# driver.net
KiCad netlist of a schematic drawn in EAGLE
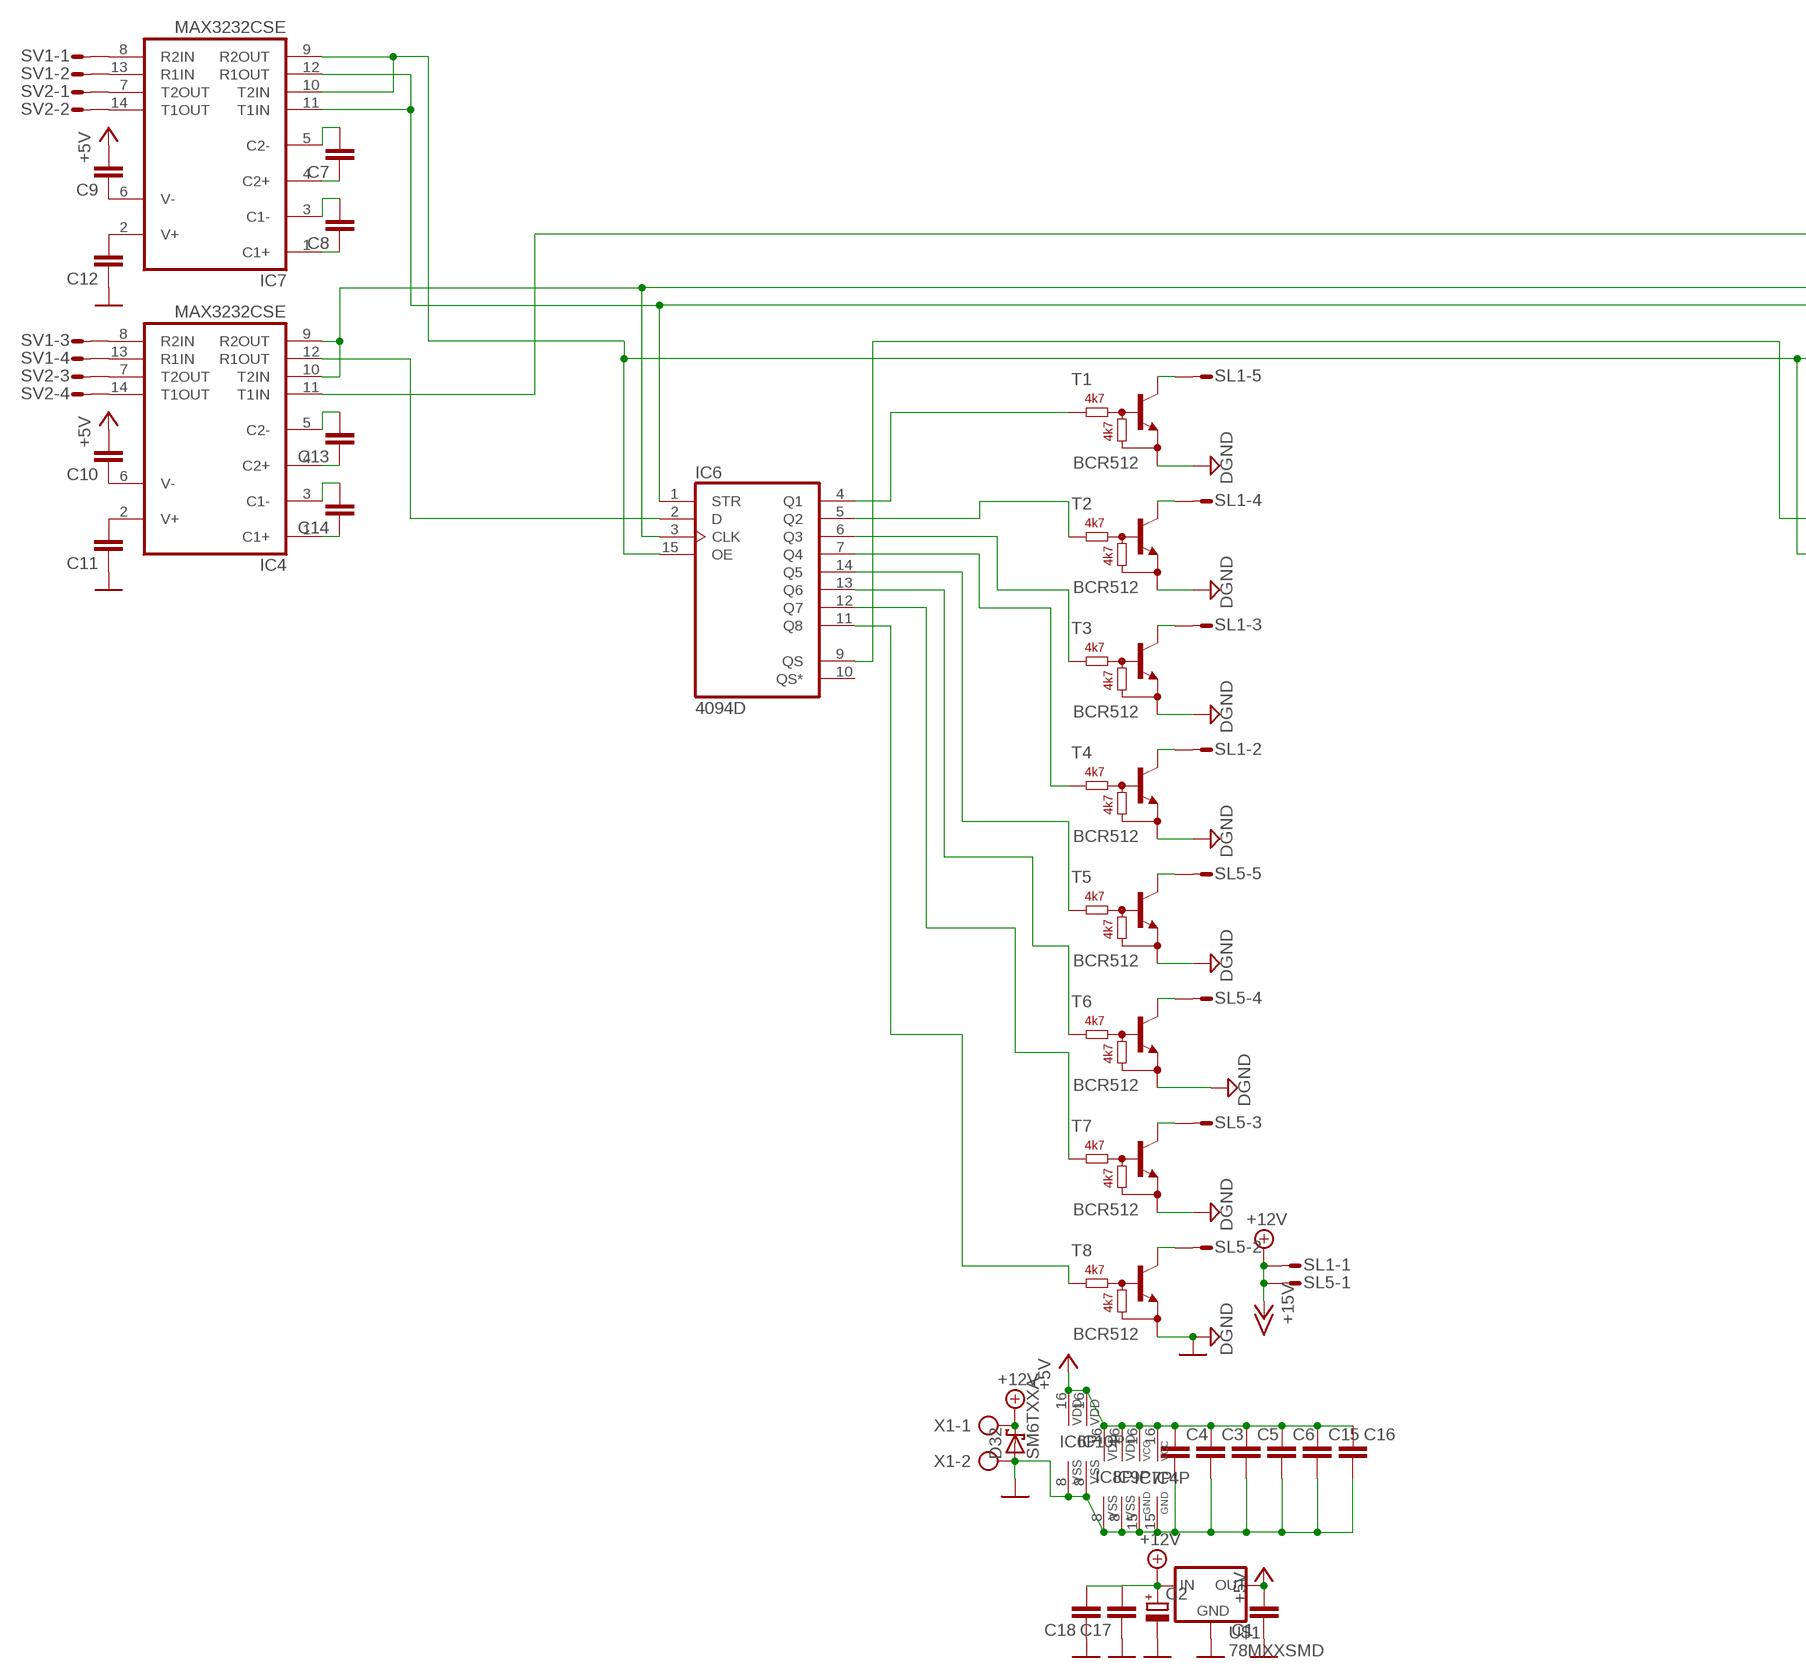
[diagram p0: schematic, sheet 1, part 1 of 2]
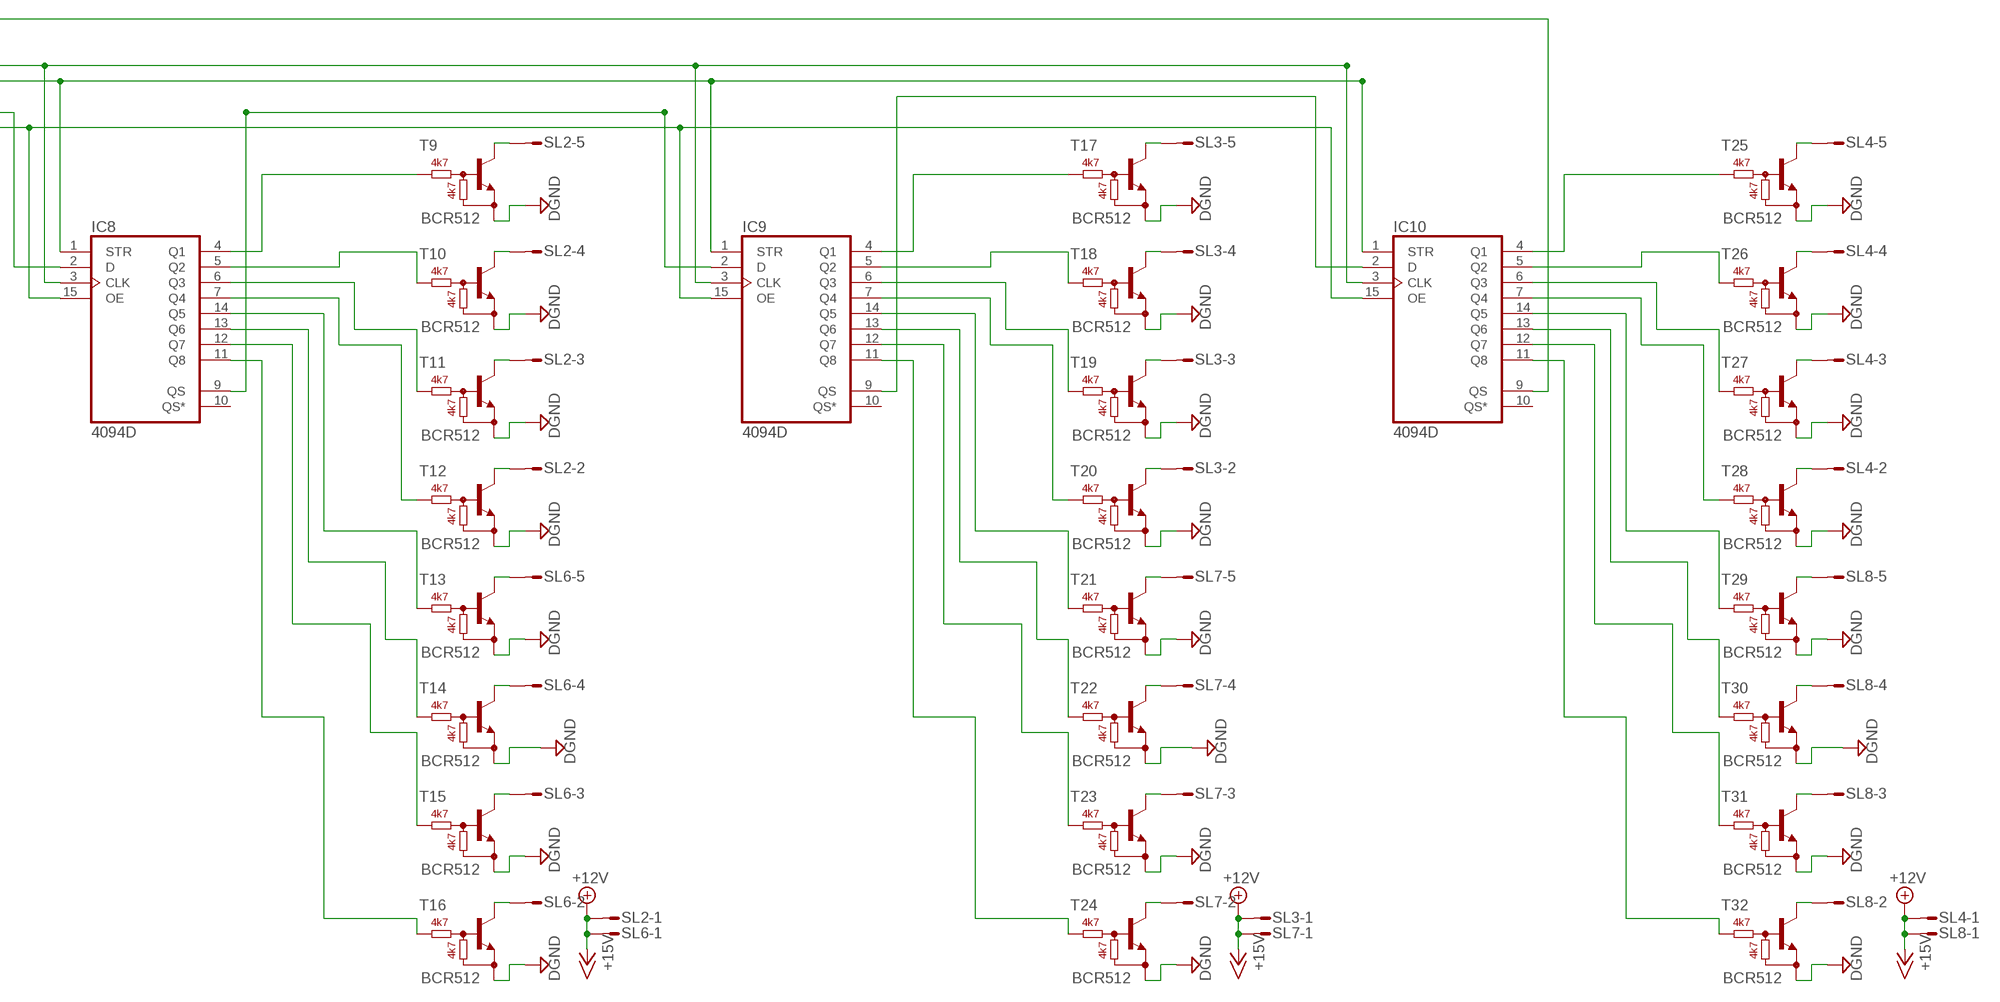
[diagram p1: schematic, sheet 1, part 2 of 2]

(export (version "E")
  (design (tool "Eeschema 10.0.6"))
  (components
    (comp (ref "C1")
      (value "C-EUC0603")
      (footprint "eagle-import:C0603")
      (libsource (lib "eagle-import") (part "C-EUC0603"))
    )
    (comp (ref "C2")
      (value "CPOL-EUSMCD")
      (footprint "eagle-import:SMC_D")
      (libsource (lib "eagle-import") (part "CPOL-EUSMCD"))
    )
    (comp (ref "C3")
      (value "C-EUC0603")
      (footprint "eagle-import:C0603")
      (libsource (lib "eagle-import") (part "C-EUC0603"))
    )
    (comp (ref "C4")
      (value "C-EUC0603")
      (footprint "eagle-import:C0603")
      (libsource (lib "eagle-import") (part "C-EUC0603"))
    )
    (comp (ref "C5")
      (value "C-EUC0603")
      (footprint "eagle-import:C0603")
      (libsource (lib "eagle-import") (part "C-EUC0603"))
    )
    (comp (ref "C6")
      (value "C-EUC0603")
      (footprint "eagle-import:C0603")
      (libsource (lib "eagle-import") (part "C-EUC0603"))
    )
    (comp (ref "C7")
      (value "C-EUC0603")
      (footprint "eagle-import:C0603")
      (libsource (lib "eagle-import") (part "C-EUC0603"))
    )
    (comp (ref "C8")
      (value "C-EUC0603")
      (footprint "eagle-import:C0603")
      (libsource (lib "eagle-import") (part "C-EUC0603"))
    )
    (comp (ref "C9")
      (value "C-EUC0603")
      (footprint "eagle-import:C0603")
      (libsource (lib "eagle-import") (part "C-EUC0603"))
    )
    (comp (ref "C10")
      (value "C-EUC0603")
      (footprint "eagle-import:C0603")
      (libsource (lib "eagle-import") (part "C-EUC0603"))
    )
    (comp (ref "C11")
      (value "C-EUC0603")
      (footprint "eagle-import:C0603")
      (libsource (lib "eagle-import") (part "C-EUC0603"))
    )
    (comp (ref "C12")
      (value "C-EUC0603")
      (footprint "eagle-import:C0603")
      (libsource (lib "eagle-import") (part "C-EUC0603"))
    )
    (comp (ref "C13")
      (value "C-EUC0603")
      (footprint "eagle-import:C0603")
      (libsource (lib "eagle-import") (part "C-EUC0603"))
    )
    (comp (ref "C14")
      (value "C-EUC0603")
      (footprint "eagle-import:C0603")
      (libsource (lib "eagle-import") (part "C-EUC0603"))
    )
    (comp (ref "C15")
      (value "C-EUC0603")
      (footprint "eagle-import:C0603")
      (libsource (lib "eagle-import") (part "C-EUC0603"))
    )
    (comp (ref "C16")
      (value "C-EUC0603")
      (footprint "eagle-import:C0603")
      (libsource (lib "eagle-import") (part "C-EUC0603"))
    )
    (comp (ref "C17")
      (value "C-EUC0603")
      (footprint "eagle-import:C0603")
      (libsource (lib "eagle-import") (part "C-EUC0603"))
    )
    (comp (ref "C18")
      (value "C-EUC0603")
      (footprint "eagle-import:C0603")
      (libsource (lib "eagle-import") (part "C-EUC0603"))
    )
    (comp (ref "D32")
      (value "SM6TXXA")
      (footprint "eagle-import:SMB")
      (libsource (lib "eagle-import") (part "SM6TXXA"))
    )
    (comp (ref "IC4")
      (value "MAX3232CSE")
      (footprint "eagle-import:SO16")
      (fields (field (name "OC_FARNELL") "1470443"))
      (libsource (lib "eagle-import") (part "MAX3232SEC"))
    )
    (comp (ref "IC6")
      (value "4094D")
      (footprint "eagle-import:SO16")
      (fields (field (name "OC_FARNELL") "1740132"))
      (libsource (lib "eagle-import") (part "4094D"))
    )
    (comp (ref "IC7")
      (value "MAX3232CSE")
      (footprint "eagle-import:SO16")
      (fields (field (name "OC_FARNELL") "1470443"))
      (libsource (lib "eagle-import") (part "MAX3232SEC"))
    )
    (comp (ref "IC8")
      (value "4094D")
      (footprint "eagle-import:SO16")
      (fields (field (name "OC_FARNELL") "1740132"))
      (libsource (lib "eagle-import") (part "4094D"))
    )
    (comp (ref "IC9")
      (value "4094D")
      (footprint "eagle-import:SO16")
      (fields (field (name "OC_FARNELL") "1740132"))
      (libsource (lib "eagle-import") (part "4094D"))
    )
    (comp (ref "IC10")
      (value "4094D")
      (footprint "eagle-import:SO16")
      (fields (field (name "OC_FARNELL") "1740132"))
      (libsource (lib "eagle-import") (part "4094D"))
    )
    (comp (ref "SL1")
      (value "M05S")
      (footprint "eagle-import:05P")
      (libsource (lib "eagle-import") (part "M05S"))
    )
    (comp (ref "SL2")
      (value "M05S")
      (footprint "eagle-import:05P")
      (libsource (lib "eagle-import") (part "M05S"))
    )
    (comp (ref "SL3")
      (value "M05S")
      (footprint "eagle-import:05P")
      (libsource (lib "eagle-import") (part "M05S"))
    )
    (comp (ref "SL4")
      (value "M05S")
      (footprint "eagle-import:05P")
      (libsource (lib "eagle-import") (part "M05S"))
    )
    (comp (ref "SL5")
      (value "M05S")
      (footprint "eagle-import:05P")
      (libsource (lib "eagle-import") (part "M05S"))
    )
    (comp (ref "SL6")
      (value "M05S")
      (footprint "eagle-import:05P")
      (libsource (lib "eagle-import") (part "M05S"))
    )
    (comp (ref "SL7")
      (value "M05S")
      (footprint "eagle-import:05P")
      (libsource (lib "eagle-import") (part "M05S"))
    )
    (comp (ref "SL8")
      (value "M05S")
      (footprint "eagle-import:05P")
      (libsource (lib "eagle-import") (part "M05S"))
    )
    (comp (ref "SV1")
      (value "S04P")
      (footprint "eagle-import:S04P")
      (libsource (lib "eagle-import") (part "S04P"))
    )
    (comp (ref "SV2")
      (value "S04P")
      (footprint "eagle-import:S04P")
      (libsource (lib "eagle-import") (part "S04P"))
    )
    (comp (ref "T1")
      (value "BCR512")
      (footprint "eagle-import:SOT23-R_INFINEON")
      (libsource (lib "eagle-import") (part "BCR512"))
    )
    (comp (ref "T2")
      (value "BCR512")
      (footprint "eagle-import:SOT23-R_INFINEON")
      (libsource (lib "eagle-import") (part "BCR512"))
    )
    (comp (ref "T3")
      (value "BCR512")
      (footprint "eagle-import:SOT23-R_INFINEON")
      (libsource (lib "eagle-import") (part "BCR512"))
    )
    (comp (ref "T4")
      (value "BCR512")
      (footprint "eagle-import:SOT23-R_INFINEON")
      (libsource (lib "eagle-import") (part "BCR512"))
    )
    (comp (ref "T5")
      (value "BCR512")
      (footprint "eagle-import:SOT23-R_INFINEON")
      (libsource (lib "eagle-import") (part "BCR512"))
    )
    (comp (ref "T6")
      (value "BCR512")
      (footprint "eagle-import:SOT23-R_INFINEON")
      (libsource (lib "eagle-import") (part "BCR512"))
    )
    (comp (ref "T7")
      (value "BCR512")
      (footprint "eagle-import:SOT23-R_INFINEON")
      (libsource (lib "eagle-import") (part "BCR512"))
    )
    (comp (ref "T8")
      (value "BCR512")
      (footprint "eagle-import:SOT23-R_INFINEON")
      (libsource (lib "eagle-import") (part "BCR512"))
    )
    (comp (ref "T9")
      (value "BCR512")
      (footprint "eagle-import:SOT23-R_INFINEON")
      (libsource (lib "eagle-import") (part "BCR512"))
    )
    (comp (ref "T10")
      (value "BCR512")
      (footprint "eagle-import:SOT23-R_INFINEON")
      (libsource (lib "eagle-import") (part "BCR512"))
    )
    (comp (ref "T11")
      (value "BCR512")
      (footprint "eagle-import:SOT23-R_INFINEON")
      (libsource (lib "eagle-import") (part "BCR512"))
    )
    (comp (ref "T12")
      (value "BCR512")
      (footprint "eagle-import:SOT23-R_INFINEON")
      (libsource (lib "eagle-import") (part "BCR512"))
    )
    (comp (ref "T13")
      (value "BCR512")
      (footprint "eagle-import:SOT23-R_INFINEON")
      (libsource (lib "eagle-import") (part "BCR512"))
    )
    (comp (ref "T14")
      (value "BCR512")
      (footprint "eagle-import:SOT23-R_INFINEON")
      (libsource (lib "eagle-import") (part "BCR512"))
    )
    (comp (ref "T15")
      (value "BCR512")
      (footprint "eagle-import:SOT23-R_INFINEON")
      (libsource (lib "eagle-import") (part "BCR512"))
    )
    (comp (ref "T16")
      (value "BCR512")
      (footprint "eagle-import:SOT23-R_INFINEON")
      (libsource (lib "eagle-import") (part "BCR512"))
    )
    (comp (ref "T17")
      (value "BCR512")
      (footprint "eagle-import:SOT23-R_INFINEON")
      (libsource (lib "eagle-import") (part "BCR512"))
    )
    (comp (ref "T18")
      (value "BCR512")
      (footprint "eagle-import:SOT23-R_INFINEON")
      (libsource (lib "eagle-import") (part "BCR512"))
    )
    (comp (ref "T19")
      (value "BCR512")
      (footprint "eagle-import:SOT23-R_INFINEON")
      (libsource (lib "eagle-import") (part "BCR512"))
    )
    (comp (ref "T20")
      (value "BCR512")
      (footprint "eagle-import:SOT23-R_INFINEON")
      (libsource (lib "eagle-import") (part "BCR512"))
    )
    (comp (ref "T21")
      (value "BCR512")
      (footprint "eagle-import:SOT23-R_INFINEON")
      (libsource (lib "eagle-import") (part "BCR512"))
    )
    (comp (ref "T22")
      (value "BCR512")
      (footprint "eagle-import:SOT23-R_INFINEON")
      (libsource (lib "eagle-import") (part "BCR512"))
    )
    (comp (ref "T23")
      (value "BCR512")
      (footprint "eagle-import:SOT23-R_INFINEON")
      (libsource (lib "eagle-import") (part "BCR512"))
    )
    (comp (ref "T24")
      (value "BCR512")
      (footprint "eagle-import:SOT23-R_INFINEON")
      (libsource (lib "eagle-import") (part "BCR512"))
    )
    (comp (ref "T25")
      (value "BCR512")
      (footprint "eagle-import:SOT23-R_INFINEON")
      (libsource (lib "eagle-import") (part "BCR512"))
    )
    (comp (ref "T26")
      (value "BCR512")
      (footprint "eagle-import:SOT23-R_INFINEON")
      (libsource (lib "eagle-import") (part "BCR512"))
    )
    (comp (ref "T27")
      (value "BCR512")
      (footprint "eagle-import:SOT23-R_INFINEON")
      (libsource (lib "eagle-import") (part "BCR512"))
    )
    (comp (ref "T28")
      (value "BCR512")
      (footprint "eagle-import:SOT23-R_INFINEON")
      (libsource (lib "eagle-import") (part "BCR512"))
    )
    (comp (ref "T29")
      (value "BCR512")
      (footprint "eagle-import:SOT23-R_INFINEON")
      (libsource (lib "eagle-import") (part "BCR512"))
    )
    (comp (ref "T30")
      (value "BCR512")
      (footprint "eagle-import:SOT23-R_INFINEON")
      (libsource (lib "eagle-import") (part "BCR512"))
    )
    (comp (ref "T31")
      (value "BCR512")
      (footprint "eagle-import:SOT23-R_INFINEON")
      (libsource (lib "eagle-import") (part "BCR512"))
    )
    (comp (ref "T32")
      (value "BCR512")
      (footprint "eagle-import:SOT23-R_INFINEON")
      (libsource (lib "eagle-import") (part "BCR512"))
    )
    (comp (ref "U$1")
      (value "78MXXSMD")
      (footprint "eagle-import:DPACK")
      (libsource (lib "eagle-import") (part "78MXXSMD"))
    )
    (comp (ref "X1")
      (value "AK500/2")
      (footprint "eagle-import:AK500_2")
      (libsource (lib "eagle-import") (part "AK500/2"))
    )
  )
  (nets
    (net (code "1") (name "+5V") (class "Default")
      (node (ref "C1") (pin "2") (pinfunction "2_2") (pintype "passive"))
      (node (ref "C10") (pin "2") (pinfunction "2_2") (pintype "passive"))
      (node (ref "C15") (pin "1") (pinfunction "1_1") (pintype "passive"))
      (node (ref "C16") (pin "1") (pinfunction "1_1") (pintype "passive"))
      (node (ref "C3") (pin "1") (pinfunction "1_1") (pintype "passive"))
      (node (ref "C4") (pin "1") (pinfunction "1_1") (pintype "passive"))
      (node (ref "C5") (pin "1") (pinfunction "1_1") (pintype "passive"))
      (node (ref "C6") (pin "1") (pinfunction "1_1") (pintype "passive"))
      (node (ref "C9") (pin "2") (pinfunction "2_2") (pintype "passive"))
      (node (ref "IC10") (pin "16") (pinfunction "VDD_16") (pintype "power_in"))
      (node (ref "IC4") (pin "16") (pinfunction "VCC_16") (pintype "power_in"))
      (node (ref "IC6") (pin "16") (pinfunction "VDD_16") (pintype "power_in"))
      (node (ref "IC7") (pin "16") (pinfunction "VCC_16") (pintype "power_in"))
      (node (ref "IC8") (pin "16") (pinfunction "VDD_16") (pintype "power_in"))
      (node (ref "IC9") (pin "16") (pinfunction "VDD_16") (pintype "power_in"))
      (node (ref "U$1") (pin "3") (pinfunction "OUT_3") (pintype "passive"))
    )
    (net (code "2") (name "+12V") (class "Default")
      (node (ref "C17") (pin "2") (pinfunction "2_2") (pintype "passive"))
      (node (ref "C18") (pin "2") (pinfunction "2_2") (pintype "passive"))
      (node (ref "C2") (pin "+") (pinfunction "+_+") (pintype "passive"))
      (node (ref "D32") (pin "C") (pinfunction "C_C") (pintype "passive"))
      (node (ref "SL1") (pin "1") (pinfunction "S_1") (pintype "passive"))
      (node (ref "SL2") (pin "1") (pinfunction "S_1") (pintype "passive"))
      (node (ref "SL3") (pin "1") (pinfunction "S_1") (pintype "passive"))
      (node (ref "SL4") (pin "1") (pinfunction "S_1") (pintype "passive"))
      (node (ref "SL5") (pin "1") (pinfunction "S_1") (pintype "passive"))
      (node (ref "SL6") (pin "1") (pinfunction "S_1") (pintype "passive"))
      (node (ref "SL7") (pin "1") (pinfunction "S_1") (pintype "passive"))
      (node (ref "SL8") (pin "1") (pinfunction "S_1") (pintype "passive"))
      (node (ref "U$1") (pin "1") (pinfunction "IN_1") (pintype "input"))
      (node (ref "X1") (pin "1") (pinfunction "KL_1") (pintype "passive"))
    )
    (net (code "3") (name "DGND") (class "Default")
      (node (ref "C1") (pin "1") (pinfunction "1_1") (pintype "passive"))
      (node (ref "C11") (pin "1") (pinfunction "1_1") (pintype "passive"))
      (node (ref "C12") (pin "1") (pinfunction "1_1") (pintype "passive"))
      (node (ref "C15") (pin "2") (pinfunction "2_2") (pintype "passive"))
      (node (ref "C16") (pin "2") (pinfunction "2_2") (pintype "passive"))
      (node (ref "C17") (pin "1") (pinfunction "1_1") (pintype "passive"))
      (node (ref "C18") (pin "1") (pinfunction "1_1") (pintype "passive"))
      (node (ref "C2") (pin "-") (pinfunction "-_-") (pintype "passive"))
      (node (ref "C3") (pin "2") (pinfunction "2_2") (pintype "passive"))
      (node (ref "C4") (pin "2") (pinfunction "2_2") (pintype "passive"))
      (node (ref "C5") (pin "2") (pinfunction "2_2") (pintype "passive"))
      (node (ref "C6") (pin "2") (pinfunction "2_2") (pintype "passive"))
      (node (ref "D32") (pin "A") (pinfunction "A_A") (pintype "passive"))
      (node (ref "IC10") (pin "8") (pinfunction "VSS_8") (pintype "power_in"))
      (node (ref "IC4") (pin "15") (pinfunction "GND_15") (pintype "power_in"))
      (node (ref "IC6") (pin "8") (pinfunction "VSS_8") (pintype "power_in"))
      (node (ref "IC7") (pin "15") (pinfunction "GND_15") (pintype "power_in"))
      (node (ref "IC8") (pin "8") (pinfunction "VSS_8") (pintype "power_in"))
      (node (ref "IC9") (pin "8") (pinfunction "VSS_8") (pintype "power_in"))
      (node (ref "T1") (pin "2") (pinfunction "E_2") (pintype "passive"))
      (node (ref "T10") (pin "2") (pinfunction "E_2") (pintype "passive"))
      (node (ref "T11") (pin "2") (pinfunction "E_2") (pintype "passive"))
      (node (ref "T12") (pin "2") (pinfunction "E_2") (pintype "passive"))
      (node (ref "T13") (pin "2") (pinfunction "E_2") (pintype "passive"))
      (node (ref "T14") (pin "2") (pinfunction "E_2") (pintype "passive"))
      (node (ref "T15") (pin "2") (pinfunction "E_2") (pintype "passive"))
      (node (ref "T16") (pin "2") (pinfunction "E_2") (pintype "passive"))
      (node (ref "T17") (pin "2") (pinfunction "E_2") (pintype "passive"))
      (node (ref "T18") (pin "2") (pinfunction "E_2") (pintype "passive"))
      (node (ref "T19") (pin "2") (pinfunction "E_2") (pintype "passive"))
      (node (ref "T2") (pin "2") (pinfunction "E_2") (pintype "passive"))
      (node (ref "T20") (pin "2") (pinfunction "E_2") (pintype "passive"))
      (node (ref "T21") (pin "2") (pinfunction "E_2") (pintype "passive"))
      (node (ref "T22") (pin "2") (pinfunction "E_2") (pintype "passive"))
      (node (ref "T23") (pin "2") (pinfunction "E_2") (pintype "passive"))
      (node (ref "T24") (pin "2") (pinfunction "E_2") (pintype "passive"))
      (node (ref "T25") (pin "2") (pinfunction "E_2") (pintype "passive"))
      (node (ref "T26") (pin "2") (pinfunction "E_2") (pintype "passive"))
      (node (ref "T27") (pin "2") (pinfunction "E_2") (pintype "passive"))
      (node (ref "T28") (pin "2") (pinfunction "E_2") (pintype "passive"))
      (node (ref "T29") (pin "2") (pinfunction "E_2") (pintype "passive"))
      (node (ref "T3") (pin "2") (pinfunction "E_2") (pintype "passive"))
      (node (ref "T30") (pin "2") (pinfunction "E_2") (pintype "passive"))
      (node (ref "T31") (pin "2") (pinfunction "E_2") (pintype "passive"))
      (node (ref "T32") (pin "2") (pinfunction "E_2") (pintype "passive"))
      (node (ref "T4") (pin "2") (pinfunction "E_2") (pintype "passive"))
      (node (ref "T5") (pin "2") (pinfunction "E_2") (pintype "passive"))
      (node (ref "T6") (pin "2") (pinfunction "E_2") (pintype "passive"))
      (node (ref "T7") (pin "2") (pinfunction "E_2") (pintype "passive"))
      (node (ref "T8") (pin "2") (pinfunction "E_2") (pintype "passive"))
      (node (ref "T9") (pin "2") (pinfunction "E_2") (pintype "passive"))
      (node (ref "U$1") (pin "4") (pinfunction "GND_4") (pintype "input"))
      (node (ref "X1") (pin "2") (pinfunction "KL_2") (pintype "passive"))
    )
    (net (code "4") (name "Net-(IC4A-C1+)") (class "Default")
      (node (ref "C14") (pin "1") (pinfunction "1_1") (pintype "passive"))
      (node (ref "IC4") (pin "1") (pinfunction "C1+_1") (pintype "bidirectional"))
    )
    (net (code "5") (name "Net-(IC4A-C1-)") (class "Default")
      (node (ref "C14") (pin "2") (pinfunction "2_2") (pintype "passive"))
      (node (ref "IC4") (pin "3") (pinfunction "C1-_3") (pintype "bidirectional"))
    )
    (net (code "6") (name "Net-(IC4A-C2+)") (class "Default")
      (node (ref "C13") (pin "1") (pinfunction "1_1") (pintype "passive"))
      (node (ref "IC4") (pin "4") (pinfunction "C2+_4") (pintype "bidirectional"))
    )
    (net (code "7") (name "Net-(IC4A-C2-)") (class "Default")
      (node (ref "C13") (pin "2") (pinfunction "2_2") (pintype "passive"))
      (node (ref "IC4") (pin "5") (pinfunction "C2-_5") (pintype "bidirectional"))
    )
    (net (code "8") (name "Net-(IC4A-R1IN)") (class "Default")
      (node (ref "IC4") (pin "13") (pinfunction "R1IN_13") (pintype "input"))
      (node (ref "SV1") (pin "4") (pinfunction "S_4") (pintype "passive"))
    )
    (net (code "9") (name "Net-(IC4A-R1OUT)") (class "Default")
      (node (ref "IC4") (pin "12") (pinfunction "R1OUT_12") (pintype "output"))
      (node (ref "IC6") (pin "2") (pinfunction "D_2") (pintype "input"))
    )
    (net (code "10") (name "Net-(IC4A-R2IN)") (class "Default")
      (node (ref "IC4") (pin "8") (pinfunction "R2IN_8") (pintype "input"))
      (node (ref "SV1") (pin "3") (pinfunction "S_3") (pintype "passive"))
    )
    (net (code "11") (name "Net-(IC4A-T1OUT)") (class "Default")
      (node (ref "IC4") (pin "14") (pinfunction "T1OUT_14") (pintype "output"))
      (node (ref "SV2") (pin "4") (pinfunction "S_4") (pintype "passive"))
    )
    (net (code "12") (name "Net-(IC4A-T2OUT)") (class "Default")
      (node (ref "IC4") (pin "7") (pinfunction "T2OUT_7") (pintype "output"))
      (node (ref "SV2") (pin "3") (pinfunction "S_3") (pintype "passive"))
    )
    (net (code "13") (name "Net-(IC4A-V+)") (class "Default")
      (node (ref "C11") (pin "2") (pinfunction "2_2") (pintype "passive"))
      (node (ref "IC4") (pin "2") (pinfunction "V+_2") (pintype "bidirectional"))
    )
    (net (code "14") (name "Net-(IC4A-V-)") (class "Default")
      (node (ref "C10") (pin "1") (pinfunction "1_1") (pintype "passive"))
      (node (ref "IC4") (pin "6") (pinfunction "V-_6") (pintype "bidirectional"))
    )
    (net (code "15") (name "Net-(IC6A-Q1)") (class "Default")
      (node (ref "IC6") (pin "4") (pinfunction "Q1_4") (pintype "output"))
      (node (ref "T1") (pin "1") (pinfunction "B_1") (pintype "passive"))
    )
    (net (code "16") (name "Net-(IC6A-Q2)") (class "Default")
      (node (ref "IC6") (pin "5") (pinfunction "Q2_5") (pintype "output"))
      (node (ref "T2") (pin "1") (pinfunction "B_1") (pintype "passive"))
    )
    (net (code "17") (name "Net-(IC6A-Q3)") (class "Default")
      (node (ref "IC6") (pin "6") (pinfunction "Q3_6") (pintype "output"))
      (node (ref "T3") (pin "1") (pinfunction "B_1") (pintype "passive"))
    )
    (net (code "18") (name "Net-(IC6A-Q4)") (class "Default")
      (node (ref "IC6") (pin "7") (pinfunction "Q4_7") (pintype "output"))
      (node (ref "T4") (pin "1") (pinfunction "B_1") (pintype "passive"))
    )
    (net (code "19") (name "Net-(IC6A-Q5)") (class "Default")
      (node (ref "IC6") (pin "14") (pinfunction "Q5_14") (pintype "output"))
      (node (ref "T5") (pin "1") (pinfunction "B_1") (pintype "passive"))
    )
    (net (code "20") (name "Net-(IC6A-Q6)") (class "Default")
      (node (ref "IC6") (pin "13") (pinfunction "Q6_13") (pintype "output"))
      (node (ref "T6") (pin "1") (pinfunction "B_1") (pintype "passive"))
    )
    (net (code "21") (name "Net-(IC6A-Q7)") (class "Default")
      (node (ref "IC6") (pin "12") (pinfunction "Q7_12") (pintype "output"))
      (node (ref "T7") (pin "1") (pinfunction "B_1") (pintype "passive"))
    )
    (net (code "22") (name "Net-(IC6A-Q8)") (class "Default")
      (node (ref "IC6") (pin "11") (pinfunction "Q8_11") (pintype "output"))
      (node (ref "T8") (pin "1") (pinfunction "B_1") (pintype "passive"))
    )
    (net (code "23") (name "Net-(IC6A-QS)") (class "Default")
      (node (ref "IC6") (pin "9") (pinfunction "QS_9") (pintype "output"))
      (node (ref "IC8") (pin "2") (pinfunction "D_2") (pintype "input"))
    )
    (net (code "24") (name "Net-(IC7A-C1+)") (class "Default")
      (node (ref "C8") (pin "1") (pinfunction "1_1") (pintype "passive"))
      (node (ref "IC7") (pin "1") (pinfunction "C1+_1") (pintype "bidirectional"))
    )
    (net (code "25") (name "Net-(IC7A-C1-)") (class "Default")
      (node (ref "C8") (pin "2") (pinfunction "2_2") (pintype "passive"))
      (node (ref "IC7") (pin "3") (pinfunction "C1-_3") (pintype "bidirectional"))
    )
    (net (code "26") (name "Net-(IC7A-C2+)") (class "Default")
      (node (ref "C7") (pin "1") (pinfunction "1_1") (pintype "passive"))
      (node (ref "IC7") (pin "4") (pinfunction "C2+_4") (pintype "bidirectional"))
    )
    (net (code "27") (name "Net-(IC7A-C2-)") (class "Default")
      (node (ref "C7") (pin "2") (pinfunction "2_2") (pintype "passive"))
      (node (ref "IC7") (pin "5") (pinfunction "C2-_5") (pintype "bidirectional"))
    )
    (net (code "28") (name "Net-(IC7A-R1IN)") (class "Default")
      (node (ref "IC7") (pin "13") (pinfunction "R1IN_13") (pintype "input"))
      (node (ref "SV1") (pin "2") (pinfunction "S_2") (pintype "passive"))
    )
    (net (code "29") (name "Net-(IC7A-R2IN)") (class "Default")
      (node (ref "IC7") (pin "8") (pinfunction "R2IN_8") (pintype "input"))
      (node (ref "SV1") (pin "1") (pinfunction "S_1") (pintype "passive"))
    )
    (net (code "30") (name "Net-(IC7A-T1OUT)") (class "Default")
      (node (ref "IC7") (pin "14") (pinfunction "T1OUT_14") (pintype "output"))
      (node (ref "SV2") (pin "2") (pinfunction "S_2") (pintype "passive"))
    )
    (net (code "31") (name "Net-(IC7A-T2OUT)") (class "Default")
      (node (ref "IC7") (pin "7") (pinfunction "T2OUT_7") (pintype "output"))
      (node (ref "SV2") (pin "1") (pinfunction "S_1") (pintype "passive"))
    )
    (net (code "32") (name "Net-(IC7A-V+)") (class "Default")
      (node (ref "C12") (pin "2") (pinfunction "2_2") (pintype "passive"))
      (node (ref "IC7") (pin "2") (pinfunction "V+_2") (pintype "bidirectional"))
    )
    (net (code "33") (name "Net-(IC7A-V-)") (class "Default")
      (node (ref "C9") (pin "1") (pinfunction "1_1") (pintype "passive"))
      (node (ref "IC7") (pin "6") (pinfunction "V-_6") (pintype "bidirectional"))
    )
    (net (code "34") (name "Net-(IC8A-Q1)") (class "Default")
      (node (ref "IC8") (pin "4") (pinfunction "Q1_4") (pintype "output"))
      (node (ref "T9") (pin "1") (pinfunction "B_1") (pintype "passive"))
    )
    (net (code "35") (name "Net-(IC8A-Q2)") (class "Default")
      (node (ref "IC8") (pin "5") (pinfunction "Q2_5") (pintype "output"))
      (node (ref "T10") (pin "1") (pinfunction "B_1") (pintype "passive"))
    )
    (net (code "36") (name "Net-(IC8A-Q3)") (class "Default")
      (node (ref "IC8") (pin "6") (pinfunction "Q3_6") (pintype "output"))
      (node (ref "T11") (pin "1") (pinfunction "B_1") (pintype "passive"))
    )
    (net (code "37") (name "Net-(IC8A-Q4)") (class "Default")
      (node (ref "IC8") (pin "7") (pinfunction "Q4_7") (pintype "output"))
      (node (ref "T12") (pin "1") (pinfunction "B_1") (pintype "passive"))
    )
    (net (code "38") (name "Net-(IC8A-Q5)") (class "Default")
      (node (ref "IC8") (pin "14") (pinfunction "Q5_14") (pintype "output"))
      (node (ref "T13") (pin "1") (pinfunction "B_1") (pintype "passive"))
    )
    (net (code "39") (name "Net-(IC8A-Q6)") (class "Default")
      (node (ref "IC8") (pin "13") (pinfunction "Q6_13") (pintype "output"))
      (node (ref "T14") (pin "1") (pinfunction "B_1") (pintype "passive"))
    )
    (net (code "40") (name "Net-(IC8A-Q7)") (class "Default")
      (node (ref "IC8") (pin "12") (pinfunction "Q7_12") (pintype "output"))
      (node (ref "T15") (pin "1") (pinfunction "B_1") (pintype "passive"))
    )
    (net (code "41") (name "Net-(IC8A-Q8)") (class "Default")
      (node (ref "IC8") (pin "11") (pinfunction "Q8_11") (pintype "output"))
      (node (ref "T16") (pin "1") (pinfunction "B_1") (pintype "passive"))
    )
    (net (code "42") (name "Net-(IC8A-QS)") (class "Default")
      (node (ref "IC8") (pin "9") (pinfunction "QS_9") (pintype "output"))
      (node (ref "IC9") (pin "2") (pinfunction "D_2") (pintype "input"))
    )
    (net (code "43") (name "Net-(IC9A-Q1)") (class "Default")
      (node (ref "IC9") (pin "4") (pinfunction "Q1_4") (pintype "output"))
      (node (ref "T17") (pin "1") (pinfunction "B_1") (pintype "passive"))
    )
    (net (code "44") (name "Net-(IC9A-Q2)") (class "Default")
      (node (ref "IC9") (pin "5") (pinfunction "Q2_5") (pintype "output"))
      (node (ref "T18") (pin "1") (pinfunction "B_1") (pintype "passive"))
    )
    (net (code "45") (name "Net-(IC9A-Q3)") (class "Default")
      (node (ref "IC9") (pin "6") (pinfunction "Q3_6") (pintype "output"))
      (node (ref "T19") (pin "1") (pinfunction "B_1") (pintype "passive"))
    )
    (net (code "46") (name "Net-(IC9A-Q4)") (class "Default")
      (node (ref "IC9") (pin "7") (pinfunction "Q4_7") (pintype "output"))
      (node (ref "T20") (pin "1") (pinfunction "B_1") (pintype "passive"))
    )
    (net (code "47") (name "Net-(IC9A-Q5)") (class "Default")
      (node (ref "IC9") (pin "14") (pinfunction "Q5_14") (pintype "output"))
      (node (ref "T21") (pin "1") (pinfunction "B_1") (pintype "passive"))
    )
    (net (code "48") (name "Net-(IC9A-Q6)") (class "Default")
      (node (ref "IC9") (pin "13") (pinfunction "Q6_13") (pintype "output"))
      (node (ref "T22") (pin "1") (pinfunction "B_1") (pintype "passive"))
    )
    (net (code "49") (name "Net-(IC9A-Q7)") (class "Default")
      (node (ref "IC9") (pin "12") (pinfunction "Q7_12") (pintype "output"))
      (node (ref "T23") (pin "1") (pinfunction "B_1") (pintype "passive"))
    )
    (net (code "50") (name "Net-(IC9A-Q8)") (class "Default")
      (node (ref "IC9") (pin "11") (pinfunction "Q8_11") (pintype "output"))
      (node (ref "T24") (pin "1") (pinfunction "B_1") (pintype "passive"))
    )
    (net (code "51") (name "Net-(IC10A-CLK)") (class "Default")
      (node (ref "IC10") (pin "3") (pinfunction "CLK_3") (pintype "input"))
      (node (ref "IC4") (pin "10") (pinfunction "T2IN_10") (pintype "input"))
      (node (ref "IC4") (pin "9") (pinfunction "R2OUT_9") (pintype "output"))
      (node (ref "IC6") (pin "3") (pinfunction "CLK_3") (pintype "input"))
      (node (ref "IC8") (pin "3") (pinfunction "CLK_3") (pintype "input"))
      (node (ref "IC9") (pin "3") (pinfunction "CLK_3") (pintype "input"))
    )
    (net (code "52") (name "Net-(IC10A-D)") (class "Default")
      (node (ref "IC10") (pin "2") (pinfunction "D_2") (pintype "input"))
      (node (ref "IC9") (pin "9") (pinfunction "QS_9") (pintype "output"))
    )
    (net (code "53") (name "Net-(IC10A-OE)") (class "Default")
      (node (ref "IC10") (pin "15") (pinfunction "OE_15") (pintype "input"))
      (node (ref "IC6") (pin "15") (pinfunction "OE_15") (pintype "input"))
      (node (ref "IC7") (pin "10") (pinfunction "T2IN_10") (pintype "input"))
      (node (ref "IC7") (pin "9") (pinfunction "R2OUT_9") (pintype "output"))
      (node (ref "IC8") (pin "15") (pinfunction "OE_15") (pintype "input"))
      (node (ref "IC9") (pin "15") (pinfunction "OE_15") (pintype "input"))
    )
    (net (code "54") (name "Net-(IC10A-Q1)") (class "Default")
      (node (ref "IC10") (pin "4") (pinfunction "Q1_4") (pintype "output"))
      (node (ref "T25") (pin "1") (pinfunction "B_1") (pintype "passive"))
    )
    (net (code "55") (name "Net-(IC10A-Q2)") (class "Default")
      (node (ref "IC10") (pin "5") (pinfunction "Q2_5") (pintype "output"))
      (node (ref "T26") (pin "1") (pinfunction "B_1") (pintype "passive"))
    )
    (net (code "56") (name "Net-(IC10A-Q3)") (class "Default")
      (node (ref "IC10") (pin "6") (pinfunction "Q3_6") (pintype "output"))
      (node (ref "T27") (pin "1") (pinfunction "B_1") (pintype "passive"))
    )
    (net (code "57") (name "Net-(IC10A-Q4)") (class "Default")
      (node (ref "IC10") (pin "7") (pinfunction "Q4_7") (pintype "output"))
      (node (ref "T28") (pin "1") (pinfunction "B_1") (pintype "passive"))
    )
    (net (code "58") (name "Net-(IC10A-Q5)") (class "Default")
      (node (ref "IC10") (pin "14") (pinfunction "Q5_14") (pintype "output"))
      (node (ref "T29") (pin "1") (pinfunction "B_1") (pintype "passive"))
    )
    (net (code "59") (name "Net-(IC10A-Q6)") (class "Default")
      (node (ref "IC10") (pin "13") (pinfunction "Q6_13") (pintype "output"))
      (node (ref "T30") (pin "1") (pinfunction "B_1") (pintype "passive"))
    )
    (net (code "60") (name "Net-(IC10A-Q7)") (class "Default")
      (node (ref "IC10") (pin "12") (pinfunction "Q7_12") (pintype "output"))
      (node (ref "T31") (pin "1") (pinfunction "B_1") (pintype "passive"))
    )
    (net (code "61") (name "Net-(IC10A-Q8)") (class "Default")
      (node (ref "IC10") (pin "11") (pinfunction "Q8_11") (pintype "output"))
      (node (ref "T32") (pin "1") (pinfunction "B_1") (pintype "passive"))
    )
    (net (code "62") (name "Net-(IC10A-QS)") (class "Default")
      (node (ref "IC10") (pin "9") (pinfunction "QS_9") (pintype "output"))
      (node (ref "IC4") (pin "11") (pinfunction "T1IN_11") (pintype "input"))
    )
    (net (code "63") (name "Net-(IC10A-STR)") (class "Default")
      (node (ref "IC10") (pin "1") (pinfunction "STR_1") (pintype "input"))
      (node (ref "IC6") (pin "1") (pinfunction "STR_1") (pintype "input"))
      (node (ref "IC7") (pin "11") (pinfunction "T1IN_11") (pintype "input"))
      (node (ref "IC7") (pin "12") (pinfunction "R1OUT_12") (pintype "output"))
      (node (ref "IC8") (pin "1") (pinfunction "STR_1") (pintype "input"))
      (node (ref "IC9") (pin "1") (pinfunction "STR_1") (pintype "input"))
    )
    (net (code "64") (name "Net-(SL1B-S)") (class "Default")
      (node (ref "SL1") (pin "2") (pinfunction "S_2") (pintype "passive"))
      (node (ref "T4") (pin "3") (pinfunction "C_3") (pintype "passive"))
    )
    (net (code "65") (name "Net-(SL1C-S)") (class "Default")
      (node (ref "SL1") (pin "3") (pinfunction "S_3") (pintype "passive"))
      (node (ref "T3") (pin "3") (pinfunction "C_3") (pintype "passive"))
    )
    (net (code "66") (name "Net-(SL1D-S)") (class "Default")
      (node (ref "SL1") (pin "4") (pinfunction "S_4") (pintype "passive"))
      (node (ref "T2") (pin "3") (pinfunction "C_3") (pintype "passive"))
    )
    (net (code "67") (name "Net-(SL1E-S)") (class "Default")
      (node (ref "SL1") (pin "5") (pinfunction "S_5") (pintype "passive"))
      (node (ref "T1") (pin "3") (pinfunction "C_3") (pintype "passive"))
    )
    (net (code "68") (name "Net-(SL2B-S)") (class "Default")
      (node (ref "SL2") (pin "2") (pinfunction "S_2") (pintype "passive"))
      (node (ref "T12") (pin "3") (pinfunction "C_3") (pintype "passive"))
    )
    (net (code "69") (name "Net-(SL2C-S)") (class "Default")
      (node (ref "SL2") (pin "3") (pinfunction "S_3") (pintype "passive"))
      (node (ref "T11") (pin "3") (pinfunction "C_3") (pintype "passive"))
    )
    (net (code "70") (name "Net-(SL2D-S)") (class "Default")
      (node (ref "SL2") (pin "4") (pinfunction "S_4") (pintype "passive"))
      (node (ref "T10") (pin "3") (pinfunction "C_3") (pintype "passive"))
    )
    (net (code "71") (name "Net-(SL2E-S)") (class "Default")
      (node (ref "SL2") (pin "5") (pinfunction "S_5") (pintype "passive"))
      (node (ref "T9") (pin "3") (pinfunction "C_3") (pintype "passive"))
    )
    (net (code "72") (name "Net-(SL3B-S)") (class "Default")
      (node (ref "SL3") (pin "2") (pinfunction "S_2") (pintype "passive"))
      (node (ref "T20") (pin "3") (pinfunction "C_3") (pintype "passive"))
    )
    (net (code "73") (name "Net-(SL3C-S)") (class "Default")
      (node (ref "SL3") (pin "3") (pinfunction "S_3") (pintype "passive"))
      (node (ref "T19") (pin "3") (pinfunction "C_3") (pintype "passive"))
    )
    (net (code "74") (name "Net-(SL3D-S)") (class "Default")
      (node (ref "SL3") (pin "4") (pinfunction "S_4") (pintype "passive"))
      (node (ref "T18") (pin "3") (pinfunction "C_3") (pintype "passive"))
    )
    (net (code "75") (name "Net-(SL3E-S)") (class "Default")
      (node (ref "SL3") (pin "5") (pinfunction "S_5") (pintype "passive"))
      (node (ref "T17") (pin "3") (pinfunction "C_3") (pintype "passive"))
    )
    (net (code "76") (name "Net-(SL4B-S)") (class "Default")
      (node (ref "SL4") (pin "2") (pinfunction "S_2") (pintype "passive"))
      (node (ref "T28") (pin "3") (pinfunction "C_3") (pintype "passive"))
    )
    (net (code "77") (name "Net-(SL4C-S)") (class "Default")
      (node (ref "SL4") (pin "3") (pinfunction "S_3") (pintype "passive"))
      (node (ref "T27") (pin "3") (pinfunction "C_3") (pintype "passive"))
    )
    (net (code "78") (name "Net-(SL4D-S)") (class "Default")
      (node (ref "SL4") (pin "4") (pinfunction "S_4") (pintype "passive"))
      (node (ref "T26") (pin "3") (pinfunction "C_3") (pintype "passive"))
    )
    (net (code "79") (name "Net-(SL4E-S)") (class "Default")
      (node (ref "SL4") (pin "5") (pinfunction "S_5") (pintype "passive"))
      (node (ref "T25") (pin "3") (pinfunction "C_3") (pintype "passive"))
    )
    (net (code "80") (name "Net-(SL5B-S)") (class "Default")
      (node (ref "SL5") (pin "2") (pinfunction "S_2") (pintype "passive"))
      (node (ref "T8") (pin "3") (pinfunction "C_3") (pintype "passive"))
    )
    (net (code "81") (name "Net-(SL5C-S)") (class "Default")
      (node (ref "SL5") (pin "3") (pinfunction "S_3") (pintype "passive"))
      (node (ref "T7") (pin "3") (pinfunction "C_3") (pintype "passive"))
    )
    (net (code "82") (name "Net-(SL5D-S)") (class "Default")
      (node (ref "SL5") (pin "4") (pinfunction "S_4") (pintype "passive"))
      (node (ref "T6") (pin "3") (pinfunction "C_3") (pintype "passive"))
    )
    (net (code "83") (name "Net-(SL5E-S)") (class "Default")
      (node (ref "SL5") (pin "5") (pinfunction "S_5") (pintype "passive"))
      (node (ref "T5") (pin "3") (pinfunction "C_3") (pintype "passive"))
    )
    (net (code "84") (name "Net-(SL6B-S)") (class "Default")
      (node (ref "SL6") (pin "2") (pinfunction "S_2") (pintype "passive"))
      (node (ref "T16") (pin "3") (pinfunction "C_3") (pintype "passive"))
    )
    (net (code "85") (name "Net-(SL6C-S)") (class "Default")
      (node (ref "SL6") (pin "3") (pinfunction "S_3") (pintype "passive"))
      (node (ref "T15") (pin "3") (pinfunction "C_3") (pintype "passive"))
    )
    (net (code "86") (name "Net-(SL6D-S)") (class "Default")
      (node (ref "SL6") (pin "4") (pinfunction "S_4") (pintype "passive"))
      (node (ref "T14") (pin "3") (pinfunction "C_3") (pintype "passive"))
    )
    (net (code "87") (name "Net-(SL6E-S)") (class "Default")
      (node (ref "SL6") (pin "5") (pinfunction "S_5") (pintype "passive"))
      (node (ref "T13") (pin "3") (pinfunction "C_3") (pintype "passive"))
    )
    (net (code "88") (name "Net-(SL7B-S)") (class "Default")
      (node (ref "SL7") (pin "2") (pinfunction "S_2") (pintype "passive"))
      (node (ref "T24") (pin "3") (pinfunction "C_3") (pintype "passive"))
    )
    (net (code "89") (name "Net-(SL7C-S)") (class "Default")
      (node (ref "SL7") (pin "3") (pinfunction "S_3") (pintype "passive"))
      (node (ref "T23") (pin "3") (pinfunction "C_3") (pintype "passive"))
    )
    (net (code "90") (name "Net-(SL7D-S)") (class "Default")
      (node (ref "SL7") (pin "4") (pinfunction "S_4") (pintype "passive"))
      (node (ref "T22") (pin "3") (pinfunction "C_3") (pintype "passive"))
    )
    (net (code "91") (name "Net-(SL7E-S)") (class "Default")
      (node (ref "SL7") (pin "5") (pinfunction "S_5") (pintype "passive"))
      (node (ref "T21") (pin "3") (pinfunction "C_3") (pintype "passive"))
    )
    (net (code "92") (name "Net-(SL8B-S)") (class "Default")
      (node (ref "SL8") (pin "2") (pinfunction "S_2") (pintype "passive"))
      (node (ref "T32") (pin "3") (pinfunction "C_3") (pintype "passive"))
    )
    (net (code "93") (name "Net-(SL8C-S)") (class "Default")
      (node (ref "SL8") (pin "3") (pinfunction "S_3") (pintype "passive"))
      (node (ref "T31") (pin "3") (pinfunction "C_3") (pintype "passive"))
    )
    (net (code "94") (name "Net-(SL8D-S)") (class "Default")
      (node (ref "SL8") (pin "4") (pinfunction "S_4") (pintype "passive"))
      (node (ref "T30") (pin "3") (pinfunction "C_3") (pintype "passive"))
    )
    (net (code "95") (name "Net-(SL8E-S)") (class "Default")
      (node (ref "SL8") (pin "5") (pinfunction "S_5") (pintype "passive"))
      (node (ref "T29") (pin "3") (pinfunction "C_3") (pintype "passive"))
    )
    (net (code "96") (name "unconnected-(IC6A-QS*-Pad10)") (class "Default")
      (node (ref "IC6") (pin "10") (pinfunction "QS*_10") (pintype "output"))
    )
    (net (code "97") (name "unconnected-(IC8A-QS*-Pad10)") (class "Default")
      (node (ref "IC8") (pin "10") (pinfunction "QS*_10") (pintype "output"))
    )
    (net (code "98") (name "unconnected-(IC9A-QS*-Pad10)") (class "Default")
      (node (ref "IC9") (pin "10") (pinfunction "QS*_10") (pintype "output"))
    )
    (net (code "99") (name "unconnected-(IC10A-QS*-Pad10)") (class "Default")
      (node (ref "IC10") (pin "10") (pinfunction "QS*_10") (pintype "output"))
    )
  )
)
